# Test_Sled_Rocket_Schematic_EasyEDA.net
KiCad netlist of a schematic drawn in EasyEDA
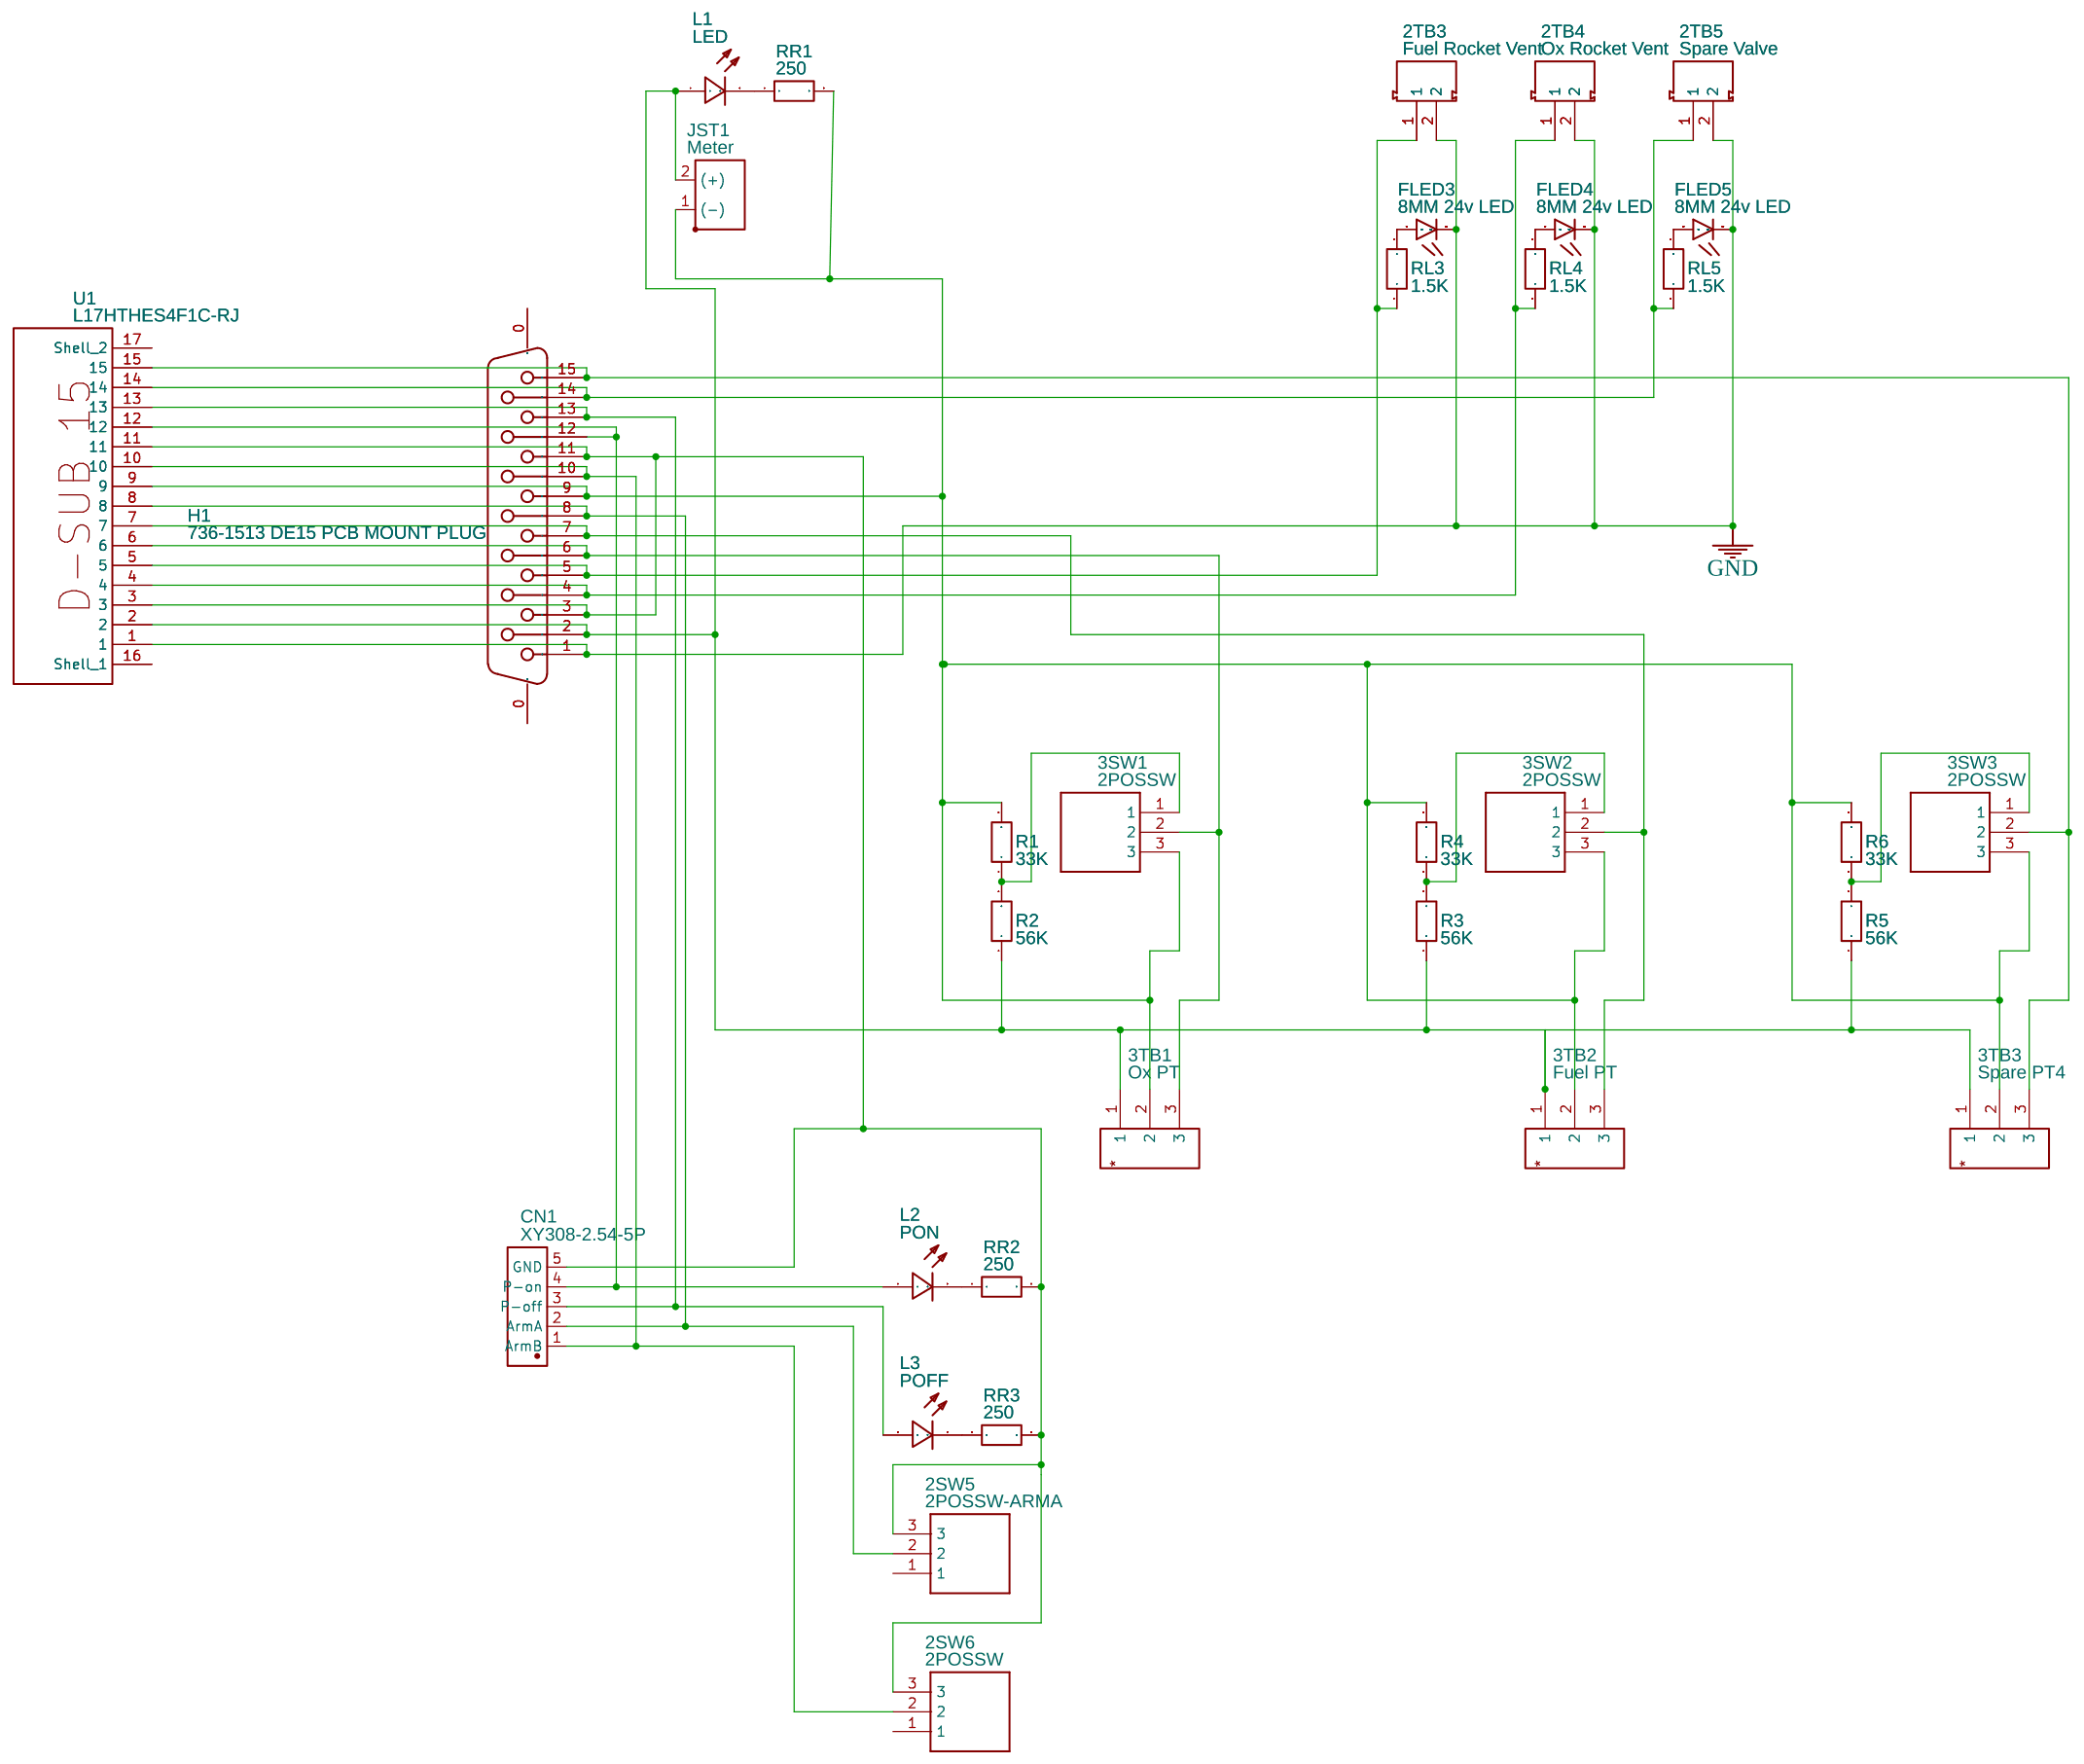
[diagram p0: schematic sheet]

(export (version "E")
  (design (tool "Eeschema 10.0.6"))
  (components
    (comp (ref "2SW5") (value "2POSSW-ARMA") (libsource (lib "") (part "MS12ANW03")))
    (comp (ref "2SW6") (value "2POSSW") (libsource (lib "") (part "MS12ANW03")))
    (comp (ref "2TB3")
      (value "Fuel Rocket Vent")
      (fields (field (name "Manufacturer Part") "1729128") (field (name "Manufacturer") "Phoenix Contact"))
      (libsource (lib "") (part "1729128"))
    )
    (comp (ref "2TB4")
      (value "Ox Rocket Vent")
      (fields (field (name "Manufacturer Part") "1729128") (field (name "Manufacturer") "Phoenix Contact"))
      (libsource (lib "") (part "1729128"))
    )
    (comp (ref "2TB5")
      (value "Spare Valve")
      (fields (field (name "Manufacturer Part") "1729128") (field (name "Manufacturer") "Phoenix Contact"))
      (libsource (lib "") (part "1729128"))
    )
    (comp (ref "3SW1") (value "2POSSW") (libsource (lib "") (part "MS12ANW03_1")))
    (comp (ref "3SW2") (value "2POSSW") (libsource (lib "") (part "MS12ANW03_1")))
    (comp (ref "3SW3") (value "2POSSW") (libsource (lib "") (part "MS12ANW03_1")))
    (comp (ref "3TB1")
      (value "Ox PT")
      (fields (field (name "Manufacturer Part") "3 Pin Screw Terminal 5.08"))
      (libsource (lib "") (part "SCREW TERMINAL 3P"))
    )
    (comp (ref "3TB2")
      (value "Fuel PT")
      (fields (field (name "Manufacturer Part") "3 Pin Screw Terminal 5.08"))
      (libsource (lib "") (part "SCREW TERMINAL 3P"))
    )
    (comp (ref "3TB3")
      (value "Spare PT4")
      (fields (field (name "Manufacturer Part") "3 Pin Screw Terminal 5.08"))
      (libsource (lib "") (part "SCREW TERMINAL 3P"))
    )
    (comp (ref "CN1")
      (value "XY308-2.54-5P")
      (fields (field (name "Manufacturer") "XINLAIYA(新莱亚)"))
      (libsource (lib "") (part "XY308-2.54-5P"))
    )
    (comp (ref "FLED3") (value "8MM 24v LED") (libsource (lib "") (part "P804JPF4D")))
    (comp (ref "FLED4") (value "8MM 24v LED") (libsource (lib "") (part "P804JPF4D")))
    (comp (ref "FLED5") (value "8MM 24v LED") (libsource (lib "") (part "P804JPF4D")))
    (comp (ref "H1")
      (value "736-1513 DE15 PCB MOUNT PLUG")
      (fields
        (field (name "Manufacturer Part") "10090926-P154XLF")
        (field (name "Manufacturer") "Amphenol FCI")
      )
      (libsource (lib "") (part "736-1513 DE15 PCB MOUNT PLUG"))
    )
    (comp (ref "JST1") (value "Meter") (libsource (lib "") (part "JST2X")))
    (comp (ref "L1")
      (value "LED")
      (fields
        (field (name "Manufacturer Part") "TJ-L3FYTGHTCGSFLC6B-A5")
        (field (name "Manufacturer") "TOGIALED")
      )
      (libsource (lib "") (part "Unknown_235_-590"))
    )
    (comp (ref "L2")
      (value "PON")
      (fields
        (field (name "Manufacturer Part") "TJ-L3FYTGHTCGSFLC6B-A5")
        (field (name "Manufacturer") "TOGIALED")
      )
      (libsource (lib "") (part "Unknown_340_15"))
    )
    (comp (ref "L3")
      (value "POFF")
      (fields
        (field (name "Manufacturer Part") "TJ-L3FYTGHTCGSFLC6B-A5")
        (field (name "Manufacturer") "TOGIALED")
      )
      (libsource (lib "") (part "Unknown_340_90"))
    )
    (comp (ref "R1")
      (value "33K")
      (fields (field (name "Manufacturer Part") "SFR03EZPF1001") (field (name "Manufacturer") "ROHM(罗姆)"))
      (libsource (lib "") (part "SFR03EZPF1001"))
    )
    (comp (ref "R2")
      (value "56K")
      (fields (field (name "Manufacturer Part") "SFR03EZPF1001") (field (name "Manufacturer") "ROHM(罗姆)"))
      (libsource (lib "") (part "SFR03EZPF1001"))
    )
    (comp (ref "R3")
      (value "56K")
      (fields (field (name "Manufacturer Part") "SFR03EZPF1001") (field (name "Manufacturer") "ROHM(罗姆)"))
      (libsource (lib "") (part "SFR03EZPF1001"))
    )
    (comp (ref "R4")
      (value "33K")
      (fields (field (name "Manufacturer Part") "SFR03EZPF1001") (field (name "Manufacturer") "ROHM(罗姆)"))
      (libsource (lib "") (part "SFR03EZPF1001"))
    )
    (comp (ref "R5")
      (value "56K")
      (fields (field (name "Manufacturer Part") "SFR03EZPF1001") (field (name "Manufacturer") "ROHM(罗姆)"))
      (libsource (lib "") (part "SFR03EZPF1001"))
    )
    (comp (ref "R6")
      (value "33K")
      (fields (field (name "Manufacturer Part") "SFR03EZPF1001") (field (name "Manufacturer") "ROHM(罗姆)"))
      (libsource (lib "") (part "SFR03EZPF1001"))
    )
    (comp (ref "RL3")
      (value "1.5K")
      (fields (field (name "Manufacturer Part") "SFR03EZPF1001") (field (name "Manufacturer") "ROHM(罗姆)"))
      (libsource (lib "") (part "SFR03EZPF1001_1"))
    )
    (comp (ref "RL4")
      (value "1.5K")
      (fields (field (name "Manufacturer Part") "SFR03EZPF1001") (field (name "Manufacturer") "ROHM(罗姆)"))
      (libsource (lib "") (part "SFR03EZPF1001_1"))
    )
    (comp (ref "RL5")
      (value "1.5K")
      (fields (field (name "Manufacturer Part") "SFR03EZPF1001") (field (name "Manufacturer") "ROHM(罗姆)"))
      (libsource (lib "") (part "SFR03EZPF1001_1"))
    )
    (comp (ref "RR1")
      (value "250")
      (fields (field (name "Manufacturer Part") "SFR03EZPF1001") (field (name "Manufacturer") "ROHM(罗姆)"))
      (libsource (lib "") (part "SFR03EZPF1001_2"))
    )
    (comp (ref "RR2")
      (value "250")
      (fields (field (name "Manufacturer Part") "SFR03EZPF1001") (field (name "Manufacturer") "ROHM(罗姆)"))
      (libsource (lib "") (part "SFR03EZPF1001_2"))
    )
    (comp (ref "RR3")
      (value "250")
      (fields (field (name "Manufacturer Part") "SFR03EZPF1001") (field (name "Manufacturer") "ROHM(罗姆)"))
      (libsource (lib "") (part "SFR03EZPF1001_2"))
    )
    (comp (ref "U1") (value "L17HTHES4F1C-RJ") (libsource (lib "") (part "L17HTHES4F1C-RJ")))
  )
  (nets
    (net (code "1") (name "GND") (class "Default")
      (node (ref "2TB3") (pin "2") (pinfunction "2_2") (pintype "unspecified"))
      (node (ref "2TB4") (pin "2") (pinfunction "2_2") (pintype "unspecified"))
      (node (ref "2TB5") (pin "2") (pinfunction "2_2") (pintype "unspecified"))
      (node (ref "FLED3") (pin "CATHODE") (pinfunction "CATHODE_CATHODE") (pintype "unspecified"))
      (node (ref "FLED4") (pin "CATHODE") (pinfunction "CATHODE_CATHODE") (pintype "unspecified"))
      (node (ref "FLED5") (pin "CATHODE") (pinfunction "CATHODE_CATHODE") (pintype "unspecified"))
      (node (ref "H1") (pin "1") (pinfunction "1_1") (pintype "input"))
      (node (ref "U1") (pin "1") (pinfunction "1_1") (pintype "unspecified"))
    )
    (net (code "2") (name "Net-(2TB3-Pad1)") (class "Default")
      (node (ref "2TB3") (pin "1") (pinfunction "1_1") (pintype "unspecified"))
      (node (ref "H1") (pin "5") (pinfunction "5_5") (pintype "input"))
      (node (ref "RL3") (pin "1") (pinfunction "1_1") (pintype "unspecified"))
      (node (ref "U1") (pin "5") (pinfunction "5_5") (pintype "unspecified"))
    )
    (net (code "3") (name "Net-(2TB4-Pad1)") (class "Default")
      (node (ref "2TB4") (pin "1") (pinfunction "1_1") (pintype "unspecified"))
      (node (ref "H1") (pin "4") (pinfunction "4_4") (pintype "input"))
      (node (ref "RL4") (pin "1") (pinfunction "1_1") (pintype "unspecified"))
      (node (ref "U1") (pin "4") (pinfunction "4_4") (pintype "unspecified"))
    )
    (net (code "4") (name "Net-(2TB5-Pad1)") (class "Default")
      (node (ref "2TB5") (pin "1") (pinfunction "1_1") (pintype "unspecified"))
      (node (ref "H1") (pin "14") (pinfunction "14_14") (pintype "input"))
      (node (ref "RL5") (pin "1") (pinfunction "1_1") (pintype "unspecified"))
      (node (ref "U1") (pin "14") (pinfunction "14_14") (pintype "unspecified"))
    )
    (net (code "5") (name "Net-(3SW1-Pad1)") (class "Default")
      (node (ref "3SW1") (pin "1") (pinfunction "1_1") (pintype "bidirectional"))
      (node (ref "R1") (pin "1") (pinfunction "1_1") (pintype "unspecified"))
      (node (ref "R2") (pin "2") (pinfunction "2_2") (pintype "unspecified"))
    )
    (net (code "6") (name "Net-(3SW1-Pad2)") (class "Default")
      (node (ref "3SW1") (pin "2") (pinfunction "2_2") (pintype "bidirectional"))
      (node (ref "3TB1") (pin "3") (pinfunction "3_3") (pintype "unspecified"))
      (node (ref "H1") (pin "6") (pinfunction "6_6") (pintype "input"))
      (node (ref "U1") (pin "6") (pinfunction "6_6") (pintype "unspecified"))
    )
    (net (code "7") (name "Net-(3SW2-Pad1)") (class "Default")
      (node (ref "3SW2") (pin "1") (pinfunction "1_1") (pintype "bidirectional"))
      (node (ref "R3") (pin "2") (pinfunction "2_2") (pintype "unspecified"))
      (node (ref "R4") (pin "1") (pinfunction "1_1") (pintype "unspecified"))
    )
    (net (code "8") (name "Net-(3SW2-Pad2)") (class "Default")
      (node (ref "3SW2") (pin "2") (pinfunction "2_2") (pintype "bidirectional"))
      (node (ref "3TB2") (pin "3") (pinfunction "3_3") (pintype "unspecified"))
      (node (ref "H1") (pin "7") (pinfunction "7_7") (pintype "input"))
      (node (ref "U1") (pin "7") (pinfunction "7_7") (pintype "unspecified"))
    )
    (net (code "9") (name "Net-(3SW3-Pad1)") (class "Default")
      (node (ref "3SW3") (pin "1") (pinfunction "1_1") (pintype "bidirectional"))
      (node (ref "R5") (pin "2") (pinfunction "2_2") (pintype "unspecified"))
      (node (ref "R6") (pin "1") (pinfunction "1_1") (pintype "unspecified"))
    )
    (net (code "10") (name "Net-(3SW3-Pad2)") (class "Default")
      (node (ref "3SW3") (pin "2") (pinfunction "2_2") (pintype "bidirectional"))
      (node (ref "3TB3") (pin "3") (pinfunction "3_3") (pintype "unspecified"))
      (node (ref "H1") (pin "15") (pinfunction "15_15") (pintype "input"))
      (node (ref "U1") (pin "15") (pinfunction "15_15") (pintype "unspecified"))
    )
    (net (code "11") (name "Net-(CN1-ArmA)") (class "Default")
      (node (ref "2SW5") (pin "2") (pinfunction "2_2") (pintype "bidirectional"))
      (node (ref "CN1") (pin "2") (pinfunction "ArmA_2") (pintype "unspecified"))
      (node (ref "H1") (pin "8") (pinfunction "8_8") (pintype "input"))
      (node (ref "U1") (pin "8") (pinfunction "8_8") (pintype "unspecified"))
    )
    (net (code "12") (name "Net-(CN1-ArmB)") (class "Default")
      (node (ref "2SW6") (pin "2") (pinfunction "2_2") (pintype "bidirectional"))
      (node (ref "CN1") (pin "1") (pinfunction "ArmB_1") (pintype "unspecified"))
      (node (ref "H1") (pin "10") (pinfunction "10_10") (pintype "input"))
      (node (ref "U1") (pin "10") (pinfunction "10_10") (pintype "unspecified"))
    )
    (net (code "13") (name "Net-(CN1-GND)") (class "Default")
      (node (ref "2SW5") (pin "3") (pinfunction "3_3") (pintype "bidirectional"))
      (node (ref "2SW6") (pin "3") (pinfunction "3_3") (pintype "bidirectional"))
      (node (ref "CN1") (pin "5") (pinfunction "GND_5") (pintype "unspecified"))
      (node (ref "H1") (pin "11") (pinfunction "11_11") (pintype "input"))
      (node (ref "H1") (pin "3") (pinfunction "3_3") (pintype "input"))
      (node (ref "RR2") (pin "2") (pinfunction "2_2") (pintype "unspecified"))
      (node (ref "RR3") (pin "2") (pinfunction "2_2") (pintype "unspecified"))
      (node (ref "U1") (pin "11") (pinfunction "11_11") (pintype "unspecified"))
      (node (ref "U1") (pin "3") (pinfunction "3_3") (pintype "unspecified"))
    )
    (net (code "14") (name "Net-(CN1-P-off)") (class "Default")
      (node (ref "CN1") (pin "3") (pinfunction "P-off_3") (pintype "unspecified"))
      (node (ref "H1") (pin "13") (pinfunction "13_13") (pintype "input"))
      (node (ref "L3") (pin "1") (pinfunction "1_1") (pintype "unspecified"))
      (node (ref "U1") (pin "13") (pinfunction "13_13") (pintype "unspecified"))
    )
    (net (code "15") (name "Net-(CN1-P-on)") (class "Default")
      (node (ref "CN1") (pin "4") (pinfunction "P-on_4") (pintype "unspecified"))
      (node (ref "H1") (pin "12") (pinfunction "12_12") (pintype "input"))
      (node (ref "L2") (pin "1") (pinfunction "1_1") (pintype "unspecified"))
      (node (ref "U1") (pin "12") (pinfunction "12_12") (pintype "unspecified"))
    )
    (net (code "16") (name "Net-(FLED3-PadANODE)") (class "Default")
      (node (ref "FLED3") (pin "ANODE") (pinfunction "ANODE_ANODE") (pintype "unspecified"))
      (node (ref "RL3") (pin "2") (pinfunction "2_2") (pintype "unspecified"))
    )
    (net (code "17") (name "Net-(FLED4-PadANODE)") (class "Default")
      (node (ref "FLED4") (pin "ANODE") (pinfunction "ANODE_ANODE") (pintype "unspecified"))
      (node (ref "RL4") (pin "2") (pinfunction "2_2") (pintype "unspecified"))
    )
    (net (code "18") (name "Net-(FLED5-PadANODE)") (class "Default")
      (node (ref "FLED5") (pin "ANODE") (pinfunction "ANODE_ANODE") (pintype "unspecified"))
      (node (ref "RL5") (pin "2") (pinfunction "2_2") (pintype "unspecified"))
    )
    (net (code "19") (name "Net-(JST1-(+))") (class "Default")
      (node (ref "3TB1") (pin "1") (pinfunction "1_1") (pintype "unspecified"))
      (node (ref "3TB2") (pin "1") (pinfunction "1_1") (pintype "unspecified"))
      (node (ref "3TB3") (pin "1") (pinfunction "1_1") (pintype "unspecified"))
      (node (ref "H1") (pin "2") (pinfunction "2_2") (pintype "input"))
      (node (ref "JST1") (pin "2") (pinfunction "(+)_2") (pintype "unspecified"))
      (node (ref "L1") (pin "1") (pinfunction "1_1") (pintype "unspecified"))
      (node (ref "R2") (pin "1") (pinfunction "1_1") (pintype "unspecified"))
      (node (ref "R3") (pin "1") (pinfunction "1_1") (pintype "unspecified"))
      (node (ref "R5") (pin "1") (pinfunction "1_1") (pintype "unspecified"))
      (node (ref "U1") (pin "2") (pinfunction "2_2") (pintype "unspecified"))
    )
    (net (code "20") (name "Net-(JST1-(-))") (class "Default")
      (node (ref "3SW1") (pin "3") (pinfunction "3_3") (pintype "bidirectional"))
      (node (ref "3SW2") (pin "3") (pinfunction "3_3") (pintype "bidirectional"))
      (node (ref "3SW3") (pin "3") (pinfunction "3_3") (pintype "bidirectional"))
      (node (ref "3TB1") (pin "2") (pinfunction "2_2") (pintype "unspecified"))
      (node (ref "3TB2") (pin "2") (pinfunction "2_2") (pintype "unspecified"))
      (node (ref "3TB3") (pin "2") (pinfunction "2_2") (pintype "unspecified"))
      (node (ref "H1") (pin "9") (pinfunction "9_9") (pintype "input"))
      (node (ref "JST1") (pin "1") (pinfunction "(-)_1") (pintype "unspecified"))
      (node (ref "R1") (pin "2") (pinfunction "2_2") (pintype "unspecified"))
      (node (ref "R4") (pin "2") (pinfunction "2_2") (pintype "unspecified"))
      (node (ref "R6") (pin "2") (pinfunction "2_2") (pintype "unspecified"))
      (node (ref "RR1") (pin "2") (pinfunction "2_2") (pintype "unspecified"))
      (node (ref "U1") (pin "9") (pinfunction "9_9") (pintype "unspecified"))
    )
    (net (code "21") (name "Net-(L1-Pad2)") (class "Default")
      (node (ref "L1") (pin "2") (pinfunction "2_2") (pintype "unspecified"))
      (node (ref "RR1") (pin "1") (pinfunction "1_1") (pintype "unspecified"))
    )
    (net (code "22") (name "Net-(L2-Pad2)") (class "Default")
      (node (ref "L2") (pin "2") (pinfunction "2_2") (pintype "unspecified"))
      (node (ref "RR2") (pin "1") (pinfunction "1_1") (pintype "unspecified"))
    )
    (net (code "23") (name "Net-(L3-Pad2)") (class "Default")
      (node (ref "L3") (pin "2") (pinfunction "2_2") (pintype "unspecified"))
      (node (ref "RR3") (pin "1") (pinfunction "1_1") (pintype "unspecified"))
    )
    (net (code "24") (name "unconnected-(2SW5-Pad1)") (class "Default")
      (node (ref "2SW5") (pin "1") (pinfunction "1_1") (pintype "bidirectional"))
    )
    (net (code "25") (name "unconnected-(2SW6-Pad1)") (class "Default")
      (node (ref "2SW6") (pin "1") (pinfunction "1_1") (pintype "bidirectional"))
    )
    (net (code "26") (name "unconnected-(H1-Pad0)") (class "Default")
      (node (ref "H1") (pin "0") (pinfunction "0_0") (pintype "input"))
    )
    (net (code "27") (name "unconnected-(H1-Pad0)_1") (class "Default")
      (node (ref "H1") (pin "0") (pinfunction "0_0") (pintype "input"))
    )
    (net (code "28") (name "unconnected-(U1-Shell_1-Pad16)") (class "Default")
      (node (ref "U1") (pin "16") (pinfunction "Shell_1_16") (pintype "unspecified"))
    )
    (net (code "29") (name "unconnected-(U1-Shell_2-Pad17)") (class "Default")
      (node (ref "U1") (pin "17") (pinfunction "Shell_2_17") (pintype "unspecified"))
    )
  )
)
